# RFM69_FlexyPin_Shield_0-E-shaped.net
KiCad netlist of a schematic drawn in EAGLE
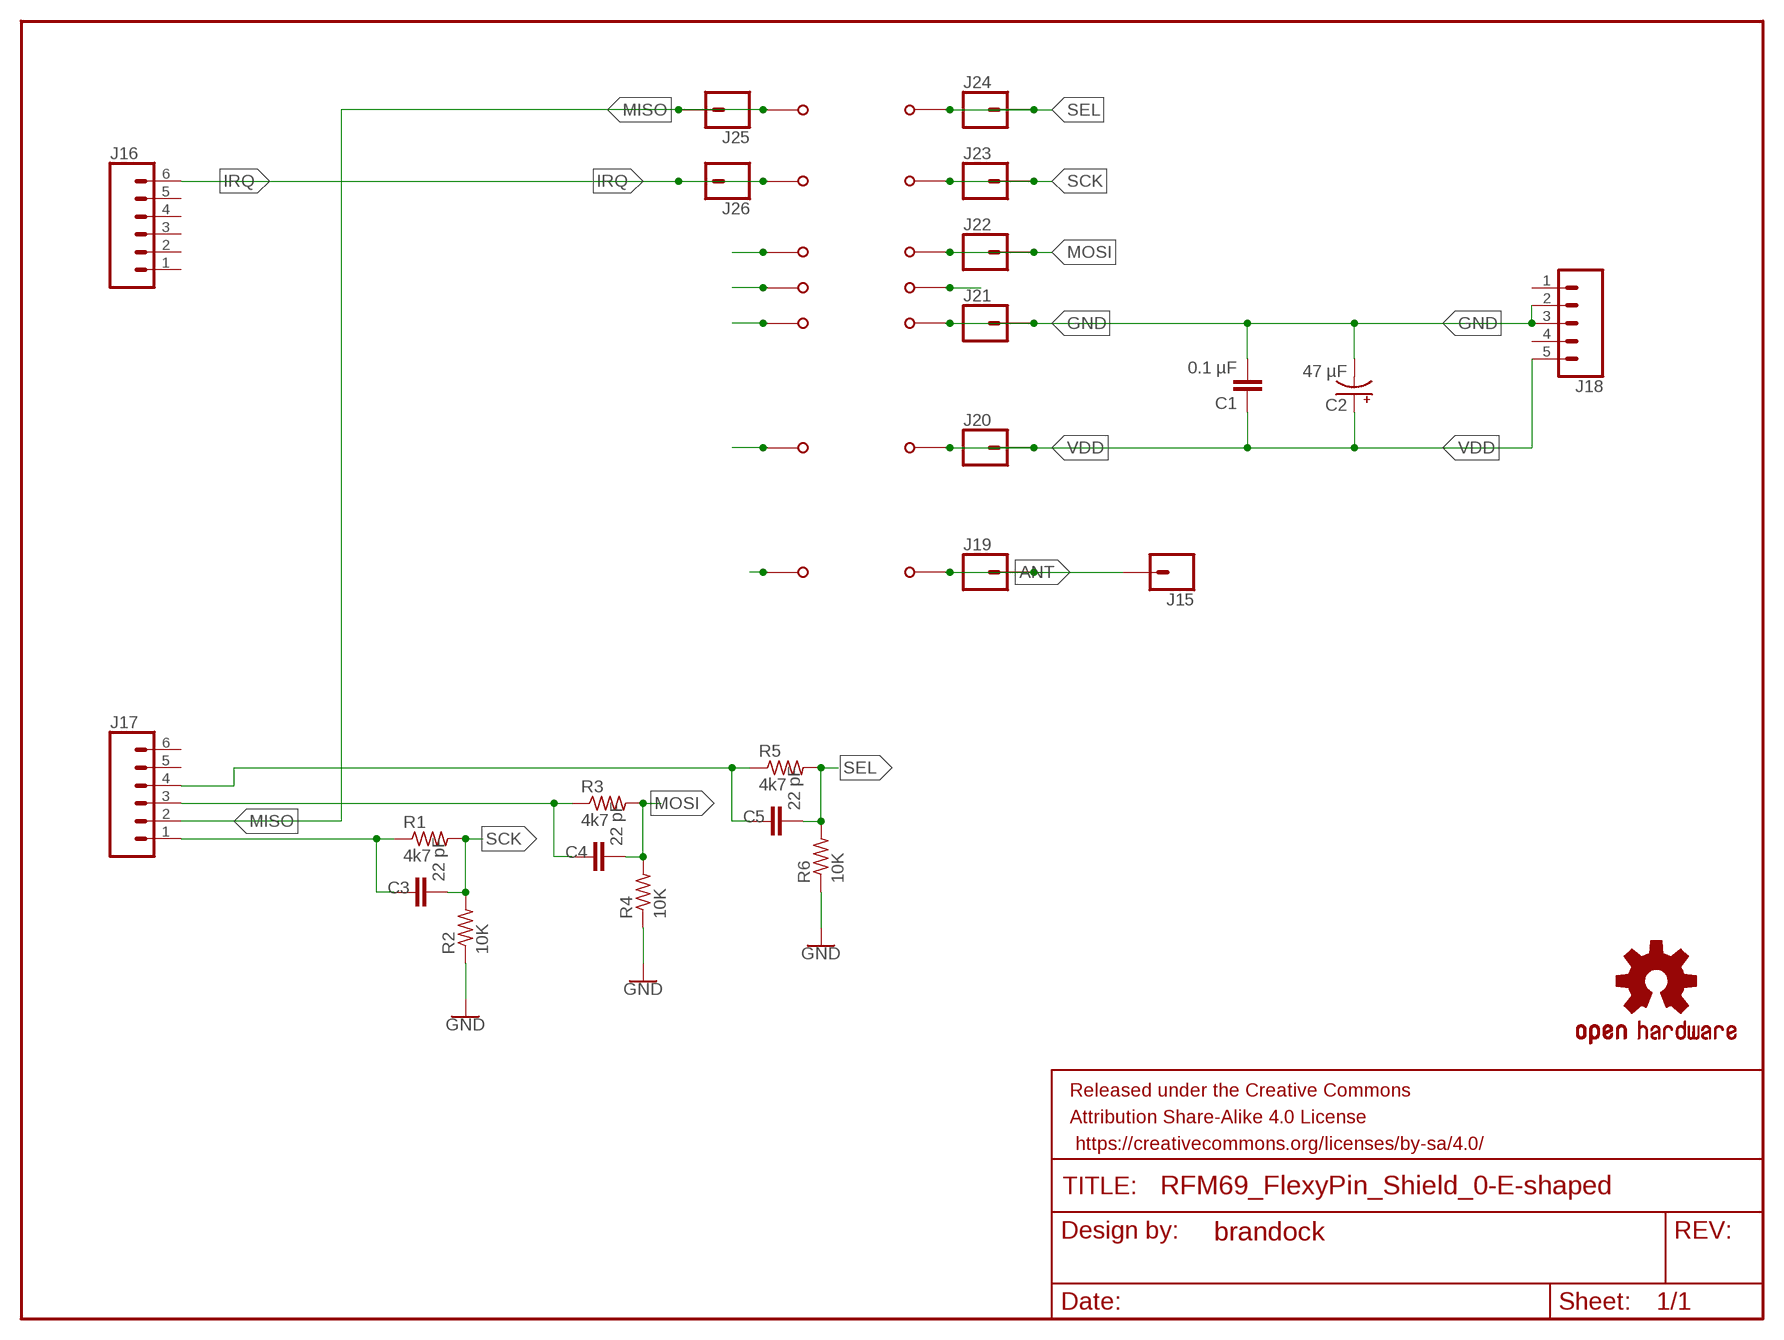
[diagram p0: schematic, sheet 1]

(export (version "E")
  (design (tool "Eeschema 10.0.6"))
  (components
    (comp (ref "C1")
      (value "0.1 µF")
      (footprint "eagle-import:C025-024X044")
      (libsource (lib "eagle-import") (part "C-EU025-024X044"))
    )
    (comp (ref "C2")
      (value "47 µF")
      (footprint "eagle-import:E2,5-6")
      (libsource (lib "eagle-import") (part "CPOL-USE2.5-6"))
    )
    (comp (ref "C3")
      (value "22 pF")
      (footprint "eagle-import:C025-024X044")
      (libsource (lib "eagle-import") (part "C-EU025-024X044"))
    )
    (comp (ref "C4")
      (value "22 pF")
      (footprint "eagle-import:C025-024X044")
      (libsource (lib "eagle-import") (part "C-EU025-024X044"))
    )
    (comp (ref "C5")
      (value "22 pF")
      (footprint "eagle-import:C025-024X044")
      (libsource (lib "eagle-import") (part "C-EU025-024X044"))
    )
    (comp (ref "FRAME1")
      (value "FRAME-LETTERNO_PACKAGE")
      (footprint "eagle-import:DUMMY")
      (fields (field (name "DESIGNER") "Nobody") (field (name "DESIGNER_1") "brandock"))
      (libsource (lib "eagle-import") (part "FRAME-LETTERNO_PACKAGE"))
    )
    (comp (ref "J1")
      (value "FLEXYPIN")
      (footprint "eagle-import:FLEXYPIN")
      (libsource (lib "eagle-import") (part "FLEXYPIN"))
    )
    (comp (ref "J2")
      (value "FLEXYPIN")
      (footprint "eagle-import:FLEXYPIN")
      (libsource (lib "eagle-import") (part "FLEXYPIN"))
    )
    (comp (ref "J3")
      (value "FLEXYPIN")
      (footprint "eagle-import:FLEXYPIN")
      (libsource (lib "eagle-import") (part "FLEXYPIN"))
    )
    (comp (ref "J4")
      (value "FLEXYPIN")
      (footprint "eagle-import:FLEXYPIN")
      (libsource (lib "eagle-import") (part "FLEXYPIN"))
    )
    (comp (ref "J5")
      (value "FLEXYPIN")
      (footprint "eagle-import:FLEXYPIN")
      (libsource (lib "eagle-import") (part "FLEXYPIN"))
    )
    (comp (ref "J6")
      (value "FLEXYPIN")
      (footprint "eagle-import:FLEXYPIN")
      (libsource (lib "eagle-import") (part "FLEXYPIN"))
    )
    (comp (ref "J7")
      (value "FLEXYPIN")
      (footprint "eagle-import:FLEXYPIN")
      (libsource (lib "eagle-import") (part "FLEXYPIN"))
    )
    (comp (ref "J8")
      (value "FLEXYPIN")
      (footprint "eagle-import:FLEXYPIN")
      (libsource (lib "eagle-import") (part "FLEXYPIN"))
    )
    (comp (ref "J9")
      (value "FLEXYPIN")
      (footprint "eagle-import:FLEXYPIN")
      (libsource (lib "eagle-import") (part "FLEXYPIN"))
    )
    (comp (ref "J10")
      (value "FLEXYPIN")
      (footprint "eagle-import:FLEXYPIN")
      (libsource (lib "eagle-import") (part "FLEXYPIN"))
    )
    (comp (ref "J11")
      (value "FLEXYPIN")
      (footprint "eagle-import:FLEXYPIN")
      (libsource (lib "eagle-import") (part "FLEXYPIN"))
    )
    (comp (ref "J12")
      (value "FLEXYPIN")
      (footprint "eagle-import:FLEXYPIN")
      (libsource (lib "eagle-import") (part "FLEXYPIN"))
    )
    (comp (ref "J13")
      (value "FLEXYPIN")
      (footprint "eagle-import:FLEXYPIN")
      (libsource (lib "eagle-import") (part "FLEXYPIN"))
    )
    (comp (ref "J14")
      (value "FLEXYPIN")
      (footprint "eagle-import:FLEXYPIN")
      (libsource (lib "eagle-import") (part "FLEXYPIN"))
    )
    (comp (ref "J15")
      (value "CONN_01PTH_NO_SILK_YES_STOP")
      (footprint "eagle-import:1X01_NO_SILK")
      (libsource (lib "eagle-import") (part "CONN_01PTH_NO_SILK_YES_STOP"))
    )
    (comp (ref "J16")
      (value "CONN_06LOCK")
      (footprint "eagle-import:1X06_LOCK")
      (libsource (lib "eagle-import") (part "CONN_06LOCK"))
    )
    (comp (ref "J17")
      (value "CONN_06LOCK")
      (footprint "eagle-import:1X06_LOCK")
      (libsource (lib "eagle-import") (part "CONN_06LOCK"))
    )
    (comp (ref "J18")
      (value "CONN_05LOCK")
      (footprint "eagle-import:1X05_LOCK")
      (libsource (lib "eagle-import") (part "CONN_05LOCK"))
    )
    (comp (ref "J19")
      (value "CONN_01PTH_NO_SILK_YES_STOP")
      (footprint "eagle-import:1X01_NO_SILK")
      (libsource (lib "eagle-import") (part "CONN_01PTH_NO_SILK_YES_STOP"))
    )
    (comp (ref "J20")
      (value "CONN_01PTH_NO_SILK_YES_STOP")
      (footprint "eagle-import:1X01_NO_SILK")
      (libsource (lib "eagle-import") (part "CONN_01PTH_NO_SILK_YES_STOP"))
    )
    (comp (ref "J21")
      (value "CONN_01PTH_NO_SILK_YES_STOP")
      (footprint "eagle-import:1X01_NO_SILK")
      (libsource (lib "eagle-import") (part "CONN_01PTH_NO_SILK_YES_STOP"))
    )
    (comp (ref "J22")
      (value "CONN_01PTH_NO_SILK_YES_STOP")
      (footprint "eagle-import:1X01_NO_SILK")
      (libsource (lib "eagle-import") (part "CONN_01PTH_NO_SILK_YES_STOP"))
    )
    (comp (ref "J23")
      (value "CONN_01PTH_NO_SILK_YES_STOP")
      (footprint "eagle-import:1X01_NO_SILK")
      (libsource (lib "eagle-import") (part "CONN_01PTH_NO_SILK_YES_STOP"))
    )
    (comp (ref "J24")
      (value "CONN_01PTH_NO_SILK_YES_STOP")
      (footprint "eagle-import:1X01_NO_SILK")
      (libsource (lib "eagle-import") (part "CONN_01PTH_NO_SILK_YES_STOP"))
    )
    (comp (ref "J25")
      (value "CONN_01PTH_NO_SILK_YES_STOP")
      (footprint "eagle-import:1X01_NO_SILK")
      (libsource (lib "eagle-import") (part "CONN_01PTH_NO_SILK_YES_STOP"))
    )
    (comp (ref "J26")
      (value "CONN_01PTH_NO_SILK_YES_STOP")
      (footprint "eagle-import:1X01_NO_SILK")
      (libsource (lib "eagle-import") (part "CONN_01PTH_NO_SILK_YES_STOP"))
    )
    (comp (ref "LOGO1")
      (value "OSHW-LOGOL")
      (footprint "eagle-import:OSHW-LOGO-L")
      (libsource (lib "eagle-import") (part "OSHW-LOGOL"))
    )
    (comp (ref "R1")
      (value "4k7")
      (footprint "eagle-import:0204_7")
      (libsource (lib "eagle-import") (part "R-US_0204/7"))
    )
    (comp (ref "R2")
      (value "10K")
      (footprint "eagle-import:0204_7")
      (libsource (lib "eagle-import") (part "R-US_0204/7"))
    )
    (comp (ref "R3")
      (value "4k7")
      (footprint "eagle-import:0204_7")
      (libsource (lib "eagle-import") (part "R-US_0204/7"))
    )
    (comp (ref "R4")
      (value "10K")
      (footprint "eagle-import:0204_7")
      (libsource (lib "eagle-import") (part "R-US_0204/7"))
    )
    (comp (ref "R5")
      (value "4k7")
      (footprint "eagle-import:0204_7")
      (libsource (lib "eagle-import") (part "R-US_0204/7"))
    )
    (comp (ref "R6")
      (value "10K")
      (footprint "eagle-import:0204_7")
      (libsource (lib "eagle-import") (part "R-US_0204/7"))
    )
  )
  (nets
    (net (code "1") (name "ANT") (class "Default")
      (node (ref "J14") (pin "P$1") (pinfunction "P$1_P$1") (pintype "bidirectional"))
      (node (ref "J15") (pin "1") (pinfunction "1_1") (pintype "passive"))
      (node (ref "J19") (pin "1") (pinfunction "1_1") (pintype "passive"))
    )
    (net (code "2") (name "GND") (class "Default")
      (node (ref "C1") (pin "2") (pinfunction "2_2") (pintype "passive"))
      (node (ref "C2") (pin "-") (pinfunction "-_-") (pintype "passive"))
      (node (ref "J12") (pin "P$1") (pinfunction "P$1_P$1") (pintype "bidirectional"))
      (node (ref "J18") (pin "2") (pinfunction "2_2") (pintype "passive"))
      (node (ref "J18") (pin "3") (pinfunction "3_3") (pintype "passive"))
      (node (ref "J21") (pin "1") (pinfunction "1_1") (pintype "passive"))
      (node (ref "R2") (pin "1") (pinfunction "1_1") (pintype "passive"))
      (node (ref "R4") (pin "1") (pinfunction "1_1") (pintype "passive"))
      (node (ref "R6") (pin "1") (pinfunction "1_1") (pintype "passive"))
    )
    (net (code "3") (name "IRQ") (class "Default")
      (node (ref "J16") (pin "6") (pinfunction "6_6") (pintype "passive"))
      (node (ref "J2") (pin "P$1") (pinfunction "P$1_P$1") (pintype "bidirectional"))
      (node (ref "J26") (pin "1") (pinfunction "1_1") (pintype "passive"))
    )
    (net (code "4") (name "MISO") (class "Default")
      (node (ref "J1") (pin "P$1") (pinfunction "P$1_P$1") (pintype "bidirectional"))
      (node (ref "J17") (pin "2") (pinfunction "2_2") (pintype "passive"))
      (node (ref "J25") (pin "1") (pinfunction "1_1") (pintype "passive"))
    )
    (net (code "5") (name "MOSI") (class "Default")
      (node (ref "C4") (pin "2") (pinfunction "2_2") (pintype "passive"))
      (node (ref "J10") (pin "P$1") (pinfunction "P$1_P$1") (pintype "bidirectional"))
      (node (ref "J22") (pin "1") (pinfunction "1_1") (pintype "passive"))
      (node (ref "R3") (pin "2") (pinfunction "2_2") (pintype "passive"))
      (node (ref "R4") (pin "2") (pinfunction "2_2") (pintype "passive"))
    )
    (net (code "6") (name "Net-(C3-Pad1)") (class "Default")
      (node (ref "C3") (pin "1") (pinfunction "1_1") (pintype "passive"))
      (node (ref "J17") (pin "1") (pinfunction "1_1") (pintype "passive"))
      (node (ref "R1") (pin "1") (pinfunction "1_1") (pintype "passive"))
    )
    (net (code "7") (name "Net-(C4-Pad1)") (class "Default")
      (node (ref "C4") (pin "1") (pinfunction "1_1") (pintype "passive"))
      (node (ref "J17") (pin "3") (pinfunction "3_3") (pintype "passive"))
      (node (ref "R3") (pin "1") (pinfunction "1_1") (pintype "passive"))
    )
    (net (code "8") (name "Net-(C5-Pad1)") (class "Default")
      (node (ref "C5") (pin "1") (pinfunction "1_1") (pintype "passive"))
      (node (ref "J17") (pin "4") (pinfunction "4_4") (pintype "passive"))
      (node (ref "R5") (pin "1") (pinfunction "1_1") (pintype "passive"))
    )
    (net (code "9") (name "SCK") (class "Default")
      (node (ref "C3") (pin "2") (pinfunction "2_2") (pintype "passive"))
      (node (ref "J23") (pin "1") (pinfunction "1_1") (pintype "passive"))
      (node (ref "J9") (pin "P$1") (pinfunction "P$1_P$1") (pintype "bidirectional"))
      (node (ref "R1") (pin "2") (pinfunction "2_2") (pintype "passive"))
      (node (ref "R2") (pin "2") (pinfunction "2_2") (pintype "passive"))
    )
    (net (code "10") (name "SEL") (class "Default")
      (node (ref "C5") (pin "2") (pinfunction "2_2") (pintype "passive"))
      (node (ref "J24") (pin "1") (pinfunction "1_1") (pintype "passive"))
      (node (ref "J8") (pin "P$1") (pinfunction "P$1_P$1") (pintype "bidirectional"))
      (node (ref "R5") (pin "2") (pinfunction "2_2") (pintype "passive"))
      (node (ref "R6") (pin "2") (pinfunction "2_2") (pintype "passive"))
    )
    (net (code "11") (name "VDD") (class "Default")
      (node (ref "C1") (pin "1") (pinfunction "1_1") (pintype "passive"))
      (node (ref "C2") (pin "+") (pinfunction "+_+") (pintype "passive"))
      (node (ref "J13") (pin "P$1") (pinfunction "P$1_P$1") (pintype "bidirectional"))
      (node (ref "J18") (pin "5") (pinfunction "5_5") (pintype "passive"))
      (node (ref "J20") (pin "1") (pinfunction "1_1") (pintype "passive"))
    )
    (net (code "12") (name "unconnected-(J3-PadP$1)") (class "Default")
      (node (ref "J3") (pin "P$1") (pinfunction "P$1_P$1") (pintype "bidirectional"))
    )
    (net (code "13") (name "unconnected-(J4-PadP$1)") (class "Default")
      (node (ref "J4") (pin "P$1") (pinfunction "P$1_P$1") (pintype "bidirectional"))
    )
    (net (code "14") (name "unconnected-(J5-PadP$1)") (class "Default")
      (node (ref "J5") (pin "P$1") (pinfunction "P$1_P$1") (pintype "bidirectional"))
    )
    (net (code "15") (name "unconnected-(J6-PadP$1)") (class "Default")
      (node (ref "J6") (pin "P$1") (pinfunction "P$1_P$1") (pintype "bidirectional"))
    )
    (net (code "16") (name "unconnected-(J7-PadP$1)") (class "Default")
      (node (ref "J7") (pin "P$1") (pinfunction "P$1_P$1") (pintype "bidirectional"))
    )
    (net (code "17") (name "unconnected-(J11-PadP$1)") (class "Default")
      (node (ref "J11") (pin "P$1") (pinfunction "P$1_P$1") (pintype "bidirectional"))
    )
    (net (code "18") (name "unconnected-(J16-Pad1)") (class "Default")
      (node (ref "J16") (pin "1") (pinfunction "1_1") (pintype "passive"))
    )
    (net (code "19") (name "unconnected-(J16-Pad2)") (class "Default")
      (node (ref "J16") (pin "2") (pinfunction "2_2") (pintype "passive"))
    )
    (net (code "20") (name "unconnected-(J16-Pad3)") (class "Default")
      (node (ref "J16") (pin "3") (pinfunction "3_3") (pintype "passive"))
    )
    (net (code "21") (name "unconnected-(J16-Pad4)") (class "Default")
      (node (ref "J16") (pin "4") (pinfunction "4_4") (pintype "passive"))
    )
    (net (code "22") (name "unconnected-(J16-Pad5)") (class "Default")
      (node (ref "J16") (pin "5") (pinfunction "5_5") (pintype "passive"))
    )
    (net (code "23") (name "unconnected-(J17-Pad5)") (class "Default")
      (node (ref "J17") (pin "5") (pinfunction "5_5") (pintype "passive"))
    )
    (net (code "24") (name "unconnected-(J17-Pad6)") (class "Default")
      (node (ref "J17") (pin "6") (pinfunction "6_6") (pintype "passive"))
    )
    (net (code "25") (name "unconnected-(J18-Pad1)") (class "Default")
      (node (ref "J18") (pin "1") (pinfunction "1_1") (pintype "passive"))
    )
    (net (code "26") (name "unconnected-(J18-Pad4)") (class "Default")
      (node (ref "J18") (pin "4") (pinfunction "4_4") (pintype "passive"))
    )
  )
)
